# 17-Led.net
KiCad netlist of a schematic drawn in Altium Designer
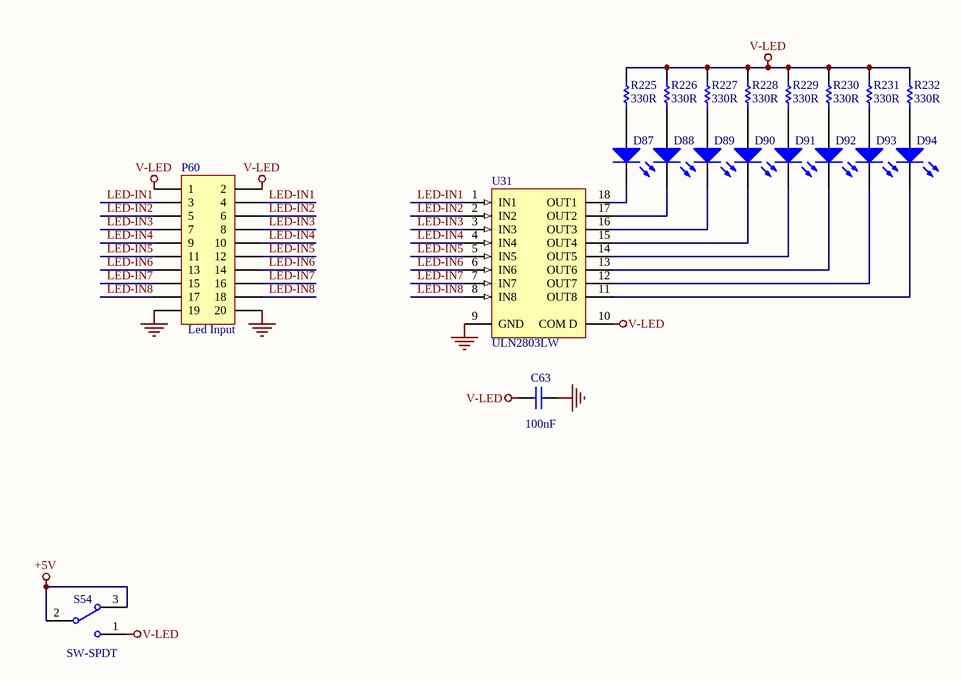
[diagram p0: 17-Led.SchDoc]

(export (version "E")
  (design (tool "Eeschema 10.0.6"))
  (components
    (comp (ref "C63")
      (value "100nF")
      (footprint "C-0805")
      (description "Capacitor")
      (fields (field (name "Comment") "104") (field (name "PUBLISHER") "Altium Limited"))
      (libsource (lib "Miscellaneous Devices") (part "Cap"))
    )
    (comp (ref "D87")
      (value "LED")
      (footprint "LED-3528")
      (description "Typical RED, GREEN, YELLOW, AMBER GaAs LED")
      (fields (field (name "PUBLISHER") "Altium Limited"))
      (libsource (lib "Miscellaneous Devices") (part "LED2"))
    )
    (comp (ref "D88")
      (value "LED")
      (footprint "LED-3528")
      (description "Typical RED, GREEN, YELLOW, AMBER GaAs LED")
      (fields (field (name "PUBLISHER") "Altium Limited"))
      (libsource (lib "Miscellaneous Devices") (part "LED2"))
    )
    (comp (ref "D89")
      (value "LED")
      (footprint "LED-3528")
      (description "Typical RED, GREEN, YELLOW, AMBER GaAs LED")
      (fields (field (name "PUBLISHER") "Altium Limited"))
      (libsource (lib "Miscellaneous Devices") (part "LED2"))
    )
    (comp (ref "D90")
      (value "LED")
      (footprint "LED-3528")
      (description "Typical RED, GREEN, YELLOW, AMBER GaAs LED")
      (fields (field (name "PUBLISHER") "Altium Limited"))
      (libsource (lib "Miscellaneous Devices") (part "LED2"))
    )
    (comp (ref "D91")
      (value "LED")
      (footprint "LED-3528")
      (description "Typical RED, GREEN, YELLOW, AMBER GaAs LED")
      (fields (field (name "PUBLISHER") "Altium Limited"))
      (libsource (lib "Miscellaneous Devices") (part "LED2"))
    )
    (comp (ref "D92")
      (value "LED")
      (footprint "LED-3528")
      (description "Typical RED, GREEN, YELLOW, AMBER GaAs LED")
      (fields (field (name "PUBLISHER") "Altium Limited"))
      (libsource (lib "Miscellaneous Devices") (part "LED2"))
    )
    (comp (ref "D93")
      (value "LED")
      (footprint "LED-3528")
      (description "Typical RED, GREEN, YELLOW, AMBER GaAs LED")
      (fields (field (name "PUBLISHER") "Altium Limited"))
      (libsource (lib "Miscellaneous Devices") (part "LED2"))
    )
    (comp (ref "D94")
      (value "LED")
      (footprint "LED-3528")
      (description "Typical RED, GREEN, YELLOW, AMBER GaAs LED")
      (fields (field (name "PUBLISHER") "Altium Limited"))
      (libsource (lib "Miscellaneous Devices") (part "LED2"))
    )
    (comp (ref "P60")
      (value "Led Input")
      (footprint "HDR2X10")
      (description "Header, 10-Pin, Dual row")
      (fields (field (name "Comment") "H10X2"))
      (libsource (lib "Miscellaneous Connectors") (part "Header 10X2"))
    )
    (comp (ref "R225")
      (value "330R")
      (footprint "R-0805")
      (description "Resistor")
      (fields (field (name "PUBLISHER") "Altium Limited"))
      (libsource (lib "Miscellaneous Devices") (part "Res1"))
    )
    (comp (ref "R226")
      (value "330R")
      (footprint "R-0805")
      (description "Resistor")
      (fields (field (name "PUBLISHER") "Altium Limited"))
      (libsource (lib "Miscellaneous Devices") (part "Res1"))
    )
    (comp (ref "R227")
      (value "330R")
      (footprint "R-0805")
      (description "Resistor")
      (fields (field (name "PUBLISHER") "Altium Limited"))
      (libsource (lib "Miscellaneous Devices") (part "Res1"))
    )
    (comp (ref "R228")
      (value "330R")
      (footprint "R-0805")
      (description "Resistor")
      (fields (field (name "PUBLISHER") "Altium Limited"))
      (libsource (lib "Miscellaneous Devices") (part "Res1"))
    )
    (comp (ref "R229")
      (value "330R")
      (footprint "R-0805")
      (description "Resistor")
      (fields (field (name "PUBLISHER") "Altium Limited"))
      (libsource (lib "Miscellaneous Devices") (part "Res1"))
    )
    (comp (ref "R230")
      (value "330R")
      (footprint "R-0805")
      (description "Resistor")
      (fields (field (name "PUBLISHER") "Altium Limited"))
      (libsource (lib "Miscellaneous Devices") (part "Res1"))
    )
    (comp (ref "R231")
      (value "330R")
      (footprint "R-0805")
      (description "Resistor")
      (fields (field (name "PUBLISHER") "Altium Limited"))
      (libsource (lib "Miscellaneous Devices") (part "Res1"))
    )
    (comp (ref "R232")
      (value "330R")
      (footprint "R-0805")
      (description "Resistor")
      (fields (field (name "PUBLISHER") "Altium Limited"))
      (libsource (lib "Miscellaneous Devices") (part "Res1"))
    )
    (comp (ref "S54")
      (value "SW-SPDT")
      (footprint "SW-DIP1SMD")
      (description "SPDT Subminiature Toggle Switch, Right Angle Mounting, Vertical Actuation")
      (fields (field (name "PUBLISHER") "Altium Limited"))
      (libsource (lib "Miscellaneous Devices") (part "SW-SPDT"))
    )
    (comp (ref "U31")
      (value "ULN2803LW")
      (footprint "sop-18")
      (description "High-Voltage, High-Current Darlington Array")
      (fields (field (name "PUBLISHER") "Altium Limited"))
      (libsource (lib "Allegro Interface Darlington Driver") (part "ULN2803LW"))
    )
  )
  (nets
    (net (code "1") (name "+5V") (class "Default")
      (node (ref "S54") (pin "2") (pinfunction "2_2") (pintype "passive"))
      (node (ref "S54") (pin "3") (pinfunction "3_3") (pintype "passive"))
    )
    (net (code "2") (name "/LED-IN1") (class "Default")
      (node (ref "P60") (pin "3") (pinfunction "3_3") (pintype "passive"))
      (node (ref "P60") (pin "4") (pinfunction "4_4") (pintype "passive"))
      (node (ref "U31") (pin "1") (pinfunction "IN1_1") (pintype "input"))
    )
    (net (code "3") (name "/LED-IN2") (class "Default")
      (node (ref "P60") (pin "5") (pinfunction "5_5") (pintype "passive"))
      (node (ref "P60") (pin "6") (pinfunction "6_6") (pintype "passive"))
      (node (ref "U31") (pin "2") (pinfunction "IN2_2") (pintype "input"))
    )
    (net (code "4") (name "/LED-IN3") (class "Default")
      (node (ref "P60") (pin "7") (pinfunction "7_7") (pintype "passive"))
      (node (ref "P60") (pin "8") (pinfunction "8_8") (pintype "passive"))
      (node (ref "U31") (pin "3") (pinfunction "IN3_3") (pintype "input"))
    )
    (net (code "5") (name "/LED-IN4") (class "Default")
      (node (ref "P60") (pin "10") (pinfunction "10_10") (pintype "passive"))
      (node (ref "P60") (pin "9") (pinfunction "9_9") (pintype "passive"))
      (node (ref "U31") (pin "4") (pinfunction "IN4_4") (pintype "input"))
    )
    (net (code "6") (name "/LED-IN5") (class "Default")
      (node (ref "P60") (pin "11") (pinfunction "11_11") (pintype "passive"))
      (node (ref "P60") (pin "12") (pinfunction "12_12") (pintype "passive"))
      (node (ref "U31") (pin "5") (pinfunction "IN5_5") (pintype "input"))
    )
    (net (code "7") (name "/LED-IN6") (class "Default")
      (node (ref "P60") (pin "13") (pinfunction "13_13") (pintype "passive"))
      (node (ref "P60") (pin "14") (pinfunction "14_14") (pintype "passive"))
      (node (ref "U31") (pin "6") (pinfunction "IN6_6") (pintype "input"))
    )
    (net (code "8") (name "/LED-IN7") (class "Default")
      (node (ref "P60") (pin "15") (pinfunction "15_15") (pintype "passive"))
      (node (ref "P60") (pin "16") (pinfunction "16_16") (pintype "passive"))
      (node (ref "U31") (pin "7") (pinfunction "IN7_7") (pintype "input"))
    )
    (net (code "9") (name "/LED-IN8") (class "Default")
      (node (ref "P60") (pin "17") (pinfunction "17_17") (pintype "passive"))
      (node (ref "P60") (pin "18") (pinfunction "18_18") (pintype "passive"))
      (node (ref "U31") (pin "8") (pinfunction "IN8_8") (pintype "input"))
    )
    (net (code "10") (name "GND") (class "Default")
      (node (ref "C63") (pin "2") (pinfunction "2_2") (pintype "passive"))
      (node (ref "P60") (pin "19") (pinfunction "19_19") (pintype "passive"))
      (node (ref "P60") (pin "20") (pinfunction "20_20") (pintype "passive"))
      (node (ref "U31") (pin "9") (pinfunction "GND_9") (pintype "power_in"))
    )
    (net (code "11") (name "Net-(D87-A)") (class "Default")
      (node (ref "D87") (pin "1") (pinfunction "A_1") (pintype "passive"))
      (node (ref "R225") (pin "1") (pinfunction "1_1") (pintype "passive"))
    )
    (net (code "12") (name "Net-(D87-K)") (class "Default")
      (node (ref "D87") (pin "2") (pinfunction "K_2") (pintype "passive"))
      (node (ref "U31") (pin "18") (pinfunction "OUT1_18") (pintype "open_collector"))
    )
    (net (code "13") (name "Net-(D88-A)") (class "Default")
      (node (ref "D88") (pin "1") (pinfunction "A_1") (pintype "passive"))
      (node (ref "R226") (pin "1") (pinfunction "1_1") (pintype "passive"))
    )
    (net (code "14") (name "Net-(D88-K)") (class "Default")
      (node (ref "D88") (pin "2") (pinfunction "K_2") (pintype "passive"))
      (node (ref "U31") (pin "17") (pinfunction "OUT2_17") (pintype "open_collector"))
    )
    (net (code "15") (name "Net-(D89-A)") (class "Default")
      (node (ref "D89") (pin "1") (pinfunction "A_1") (pintype "passive"))
      (node (ref "R227") (pin "1") (pinfunction "1_1") (pintype "passive"))
    )
    (net (code "16") (name "Net-(D89-K)") (class "Default")
      (node (ref "D89") (pin "2") (pinfunction "K_2") (pintype "passive"))
      (node (ref "U31") (pin "16") (pinfunction "OUT3_16") (pintype "open_collector"))
    )
    (net (code "17") (name "Net-(D90-A)") (class "Default")
      (node (ref "D90") (pin "1") (pinfunction "A_1") (pintype "passive"))
      (node (ref "R228") (pin "1") (pinfunction "1_1") (pintype "passive"))
    )
    (net (code "18") (name "Net-(D90-K)") (class "Default")
      (node (ref "D90") (pin "2") (pinfunction "K_2") (pintype "passive"))
      (node (ref "U31") (pin "15") (pinfunction "OUT4_15") (pintype "open_collector"))
    )
    (net (code "19") (name "Net-(D91-A)") (class "Default")
      (node (ref "D91") (pin "1") (pinfunction "A_1") (pintype "passive"))
      (node (ref "R229") (pin "1") (pinfunction "1_1") (pintype "passive"))
    )
    (net (code "20") (name "Net-(D91-K)") (class "Default")
      (node (ref "D91") (pin "2") (pinfunction "K_2") (pintype "passive"))
      (node (ref "U31") (pin "14") (pinfunction "OUT5_14") (pintype "open_collector"))
    )
    (net (code "21") (name "Net-(D92-A)") (class "Default")
      (node (ref "D92") (pin "1") (pinfunction "A_1") (pintype "passive"))
      (node (ref "R230") (pin "1") (pinfunction "1_1") (pintype "passive"))
    )
    (net (code "22") (name "Net-(D92-K)") (class "Default")
      (node (ref "D92") (pin "2") (pinfunction "K_2") (pintype "passive"))
      (node (ref "U31") (pin "13") (pinfunction "OUT6_13") (pintype "open_collector"))
    )
    (net (code "23") (name "Net-(D93-A)") (class "Default")
      (node (ref "D93") (pin "1") (pinfunction "A_1") (pintype "passive"))
      (node (ref "R231") (pin "1") (pinfunction "1_1") (pintype "passive"))
    )
    (net (code "24") (name "Net-(D93-K)") (class "Default")
      (node (ref "D93") (pin "2") (pinfunction "K_2") (pintype "passive"))
      (node (ref "U31") (pin "12") (pinfunction "OUT7_12") (pintype "open_collector"))
    )
    (net (code "25") (name "Net-(D94-A)") (class "Default")
      (node (ref "D94") (pin "1") (pinfunction "A_1") (pintype "passive"))
      (node (ref "R232") (pin "1") (pinfunction "1_1") (pintype "passive"))
    )
    (net (code "26") (name "Net-(D94-K)") (class "Default")
      (node (ref "D94") (pin "2") (pinfunction "K_2") (pintype "passive"))
      (node (ref "U31") (pin "11") (pinfunction "OUT8_11") (pintype "open_collector"))
    )
    (net (code "27") (name "V-LED") (class "Default")
      (node (ref "C63") (pin "1") (pinfunction "1_1") (pintype "passive"))
      (node (ref "P60") (pin "1") (pinfunction "1_1") (pintype "passive"))
      (node (ref "P60") (pin "2") (pinfunction "2_2") (pintype "passive"))
      (node (ref "R225") (pin "2") (pinfunction "2_2") (pintype "passive"))
      (node (ref "R226") (pin "2") (pinfunction "2_2") (pintype "passive"))
      (node (ref "R227") (pin "2") (pinfunction "2_2") (pintype "passive"))
      (node (ref "R228") (pin "2") (pinfunction "2_2") (pintype "passive"))
      (node (ref "R229") (pin "2") (pinfunction "2_2") (pintype "passive"))
      (node (ref "R230") (pin "2") (pinfunction "2_2") (pintype "passive"))
      (node (ref "R231") (pin "2") (pinfunction "2_2") (pintype "passive"))
      (node (ref "R232") (pin "2") (pinfunction "2_2") (pintype "passive"))
      (node (ref "S54") (pin "1") (pinfunction "1_1") (pintype "passive"))
      (node (ref "U31") (pin "10") (pinfunction "COM_D_10") (pintype "passive"))
    )
  )
)
